# sensor.net
KiCad netlist of a schematic drawn in Altium Designer
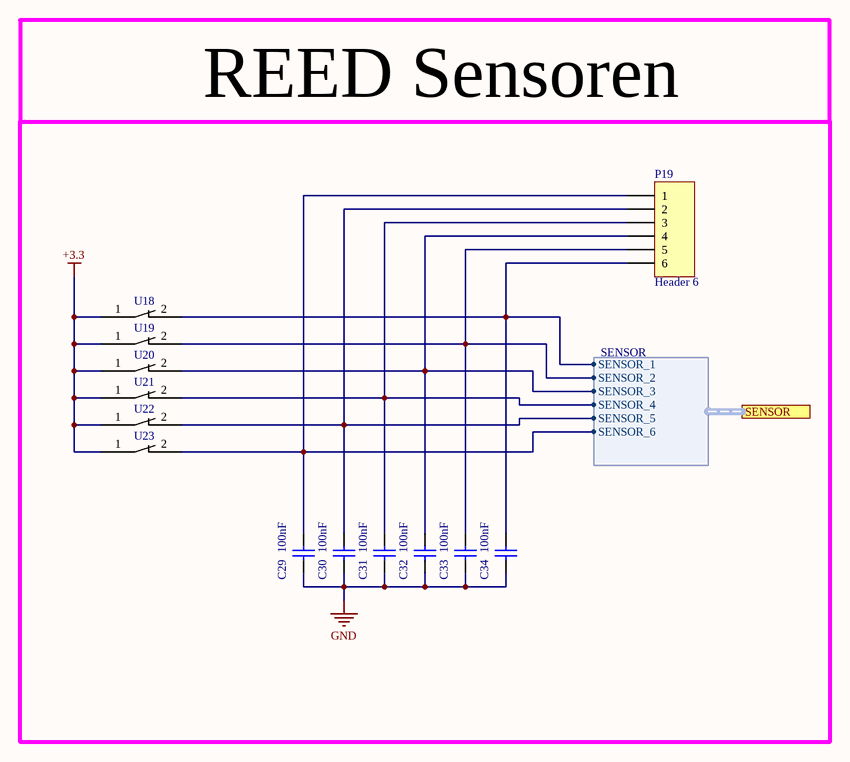
[diagram p0: sensor.SchDoc]

(export (version "E")
  (design (tool "Eeschema 10.0.6"))
  (components
    (comp (ref "C29")
      (value "100nF")
      (footprint "CAP_0402i_1005m -N")
      (description "capacitor")
      (libsource (lib "IDSC std generic parts") (part "Cap"))
    )
    (comp (ref "C30")
      (value "100nF")
      (footprint "CAP_0402i_1005m -N")
      (description "capacitor")
      (libsource (lib "IDSC std generic parts") (part "Cap"))
    )
    (comp (ref "C31")
      (value "100nF")
      (footprint "CAP_0402i_1005m -N")
      (description "capacitor")
      (libsource (lib "IDSC std generic parts") (part "Cap"))
    )
    (comp (ref "C32")
      (value "100nF")
      (footprint "CAP_0402i_1005m -N")
      (description "capacitor")
      (libsource (lib "IDSC std generic parts") (part "Cap"))
    )
    (comp (ref "C33")
      (value "100nF")
      (footprint "CAP_0402i_1005m -N")
      (description "capacitor")
      (libsource (lib "IDSC std generic parts") (part "Cap"))
    )
    (comp (ref "C34")
      (value "100nF")
      (footprint "CAP_0402i_1005m -N")
      (description "capacitor")
      (libsource (lib "IDSC std generic parts") (part "Cap"))
    )
    (comp (ref "P19")
      (value "Header 6")
      (footprint "HDR1X6")
      (description "Header, 6-Pin")
      (libsource (lib "IDSC std connectors") (part "Header 6"))
    )
    (comp (ref "U18")
      (value "reed_sensor")
      (footprint "MK 65B")
      (libsource (lib "BMA_lib") (part "reed_sensor"))
    )
    (comp (ref "U19")
      (value "reed_sensor")
      (footprint "MK 65B")
      (libsource (lib "BMA_lib") (part "reed_sensor"))
    )
    (comp (ref "U20")
      (value "reed_sensor")
      (footprint "MK 65B")
      (libsource (lib "BMA_lib") (part "reed_sensor"))
    )
    (comp (ref "U21")
      (value "reed_sensor")
      (footprint "MK 65B")
      (libsource (lib "BMA_lib") (part "reed_sensor"))
    )
    (comp (ref "U22")
      (value "reed_sensor")
      (footprint "MK 65B")
      (libsource (lib "BMA_lib") (part "reed_sensor"))
    )
    (comp (ref "U23")
      (value "reed_sensor")
      (footprint "MK 65B")
      (libsource (lib "BMA_lib") (part "reed_sensor"))
    )
  )
  (nets
    (net (code "2") (name "+3.3") (class "Default")
      (node (ref "U18") (pin "1") (pinfunction "29_1") (pintype "passive"))
      (node (ref "U19") (pin "1") (pinfunction "29_1") (pintype "passive"))
      (node (ref "U20") (pin "1") (pinfunction "29_1") (pintype "passive"))
      (node (ref "U21") (pin "1") (pinfunction "29_1") (pintype "passive"))
      (node (ref "U22") (pin "1") (pinfunction "29_1") (pintype "passive"))
      (node (ref "U23") (pin "1") (pinfunction "29_1") (pintype "passive"))
    )
    (net (code "4") (name "GND") (class "Default")
      (node (ref "C29") (pin "1") (pinfunction "1_1") (pintype "passive"))
      (node (ref "C30") (pin "1") (pinfunction "1_1") (pintype "passive"))
      (node (ref "C31") (pin "1") (pinfunction "1_1") (pintype "passive"))
      (node (ref "C32") (pin "1") (pinfunction "1_1") (pintype "passive"))
      (node (ref "C33") (pin "1") (pinfunction "1_1") (pintype "passive"))
      (node (ref "C34") (pin "1") (pinfunction "1_1") (pintype "passive"))
    )
    (net (code "5") (name "Net-(U18-30)") (class "Default")
      (node (ref "C34") (pin "2") (pinfunction "2_2") (pintype "passive"))
      (node (ref "P19") (pin "6") (pinfunction "6_6") (pintype "passive"))
      (node (ref "U18") (pin "2") (pinfunction "30_2") (pintype "passive"))
    )
    (net (code "6") (name "Net-(U19-30)") (class "Default")
      (node (ref "C33") (pin "2") (pinfunction "2_2") (pintype "passive"))
      (node (ref "P19") (pin "5") (pinfunction "5_5") (pintype "passive"))
      (node (ref "U19") (pin "2") (pinfunction "30_2") (pintype "passive"))
    )
    (net (code "7") (name "Net-(U20-30)") (class "Default")
      (node (ref "C32") (pin "2") (pinfunction "2_2") (pintype "passive"))
      (node (ref "P19") (pin "4") (pinfunction "4_4") (pintype "passive"))
      (node (ref "U20") (pin "2") (pinfunction "30_2") (pintype "passive"))
    )
    (net (code "8") (name "Net-(U21-30)") (class "Default")
      (node (ref "C31") (pin "2") (pinfunction "2_2") (pintype "passive"))
      (node (ref "P19") (pin "3") (pinfunction "3_3") (pintype "passive"))
      (node (ref "U21") (pin "2") (pinfunction "30_2") (pintype "passive"))
    )
    (net (code "9") (name "Net-(U22-30)") (class "Default")
      (node (ref "C30") (pin "2") (pinfunction "2_2") (pintype "passive"))
      (node (ref "P19") (pin "2") (pinfunction "2_2") (pintype "passive"))
      (node (ref "U22") (pin "2") (pinfunction "30_2") (pintype "passive"))
    )
    (net (code "10") (name "Net-(U23-30)") (class "Default")
      (node (ref "C29") (pin "2") (pinfunction "2_2") (pintype "passive"))
      (node (ref "P19") (pin "1") (pinfunction "1_1") (pintype "passive"))
      (node (ref "U23") (pin "2") (pinfunction "30_2") (pintype "passive"))
    )
  )
)
